# Keg_Cop.net
KiCad netlist of a schematic drawn in EAGLE
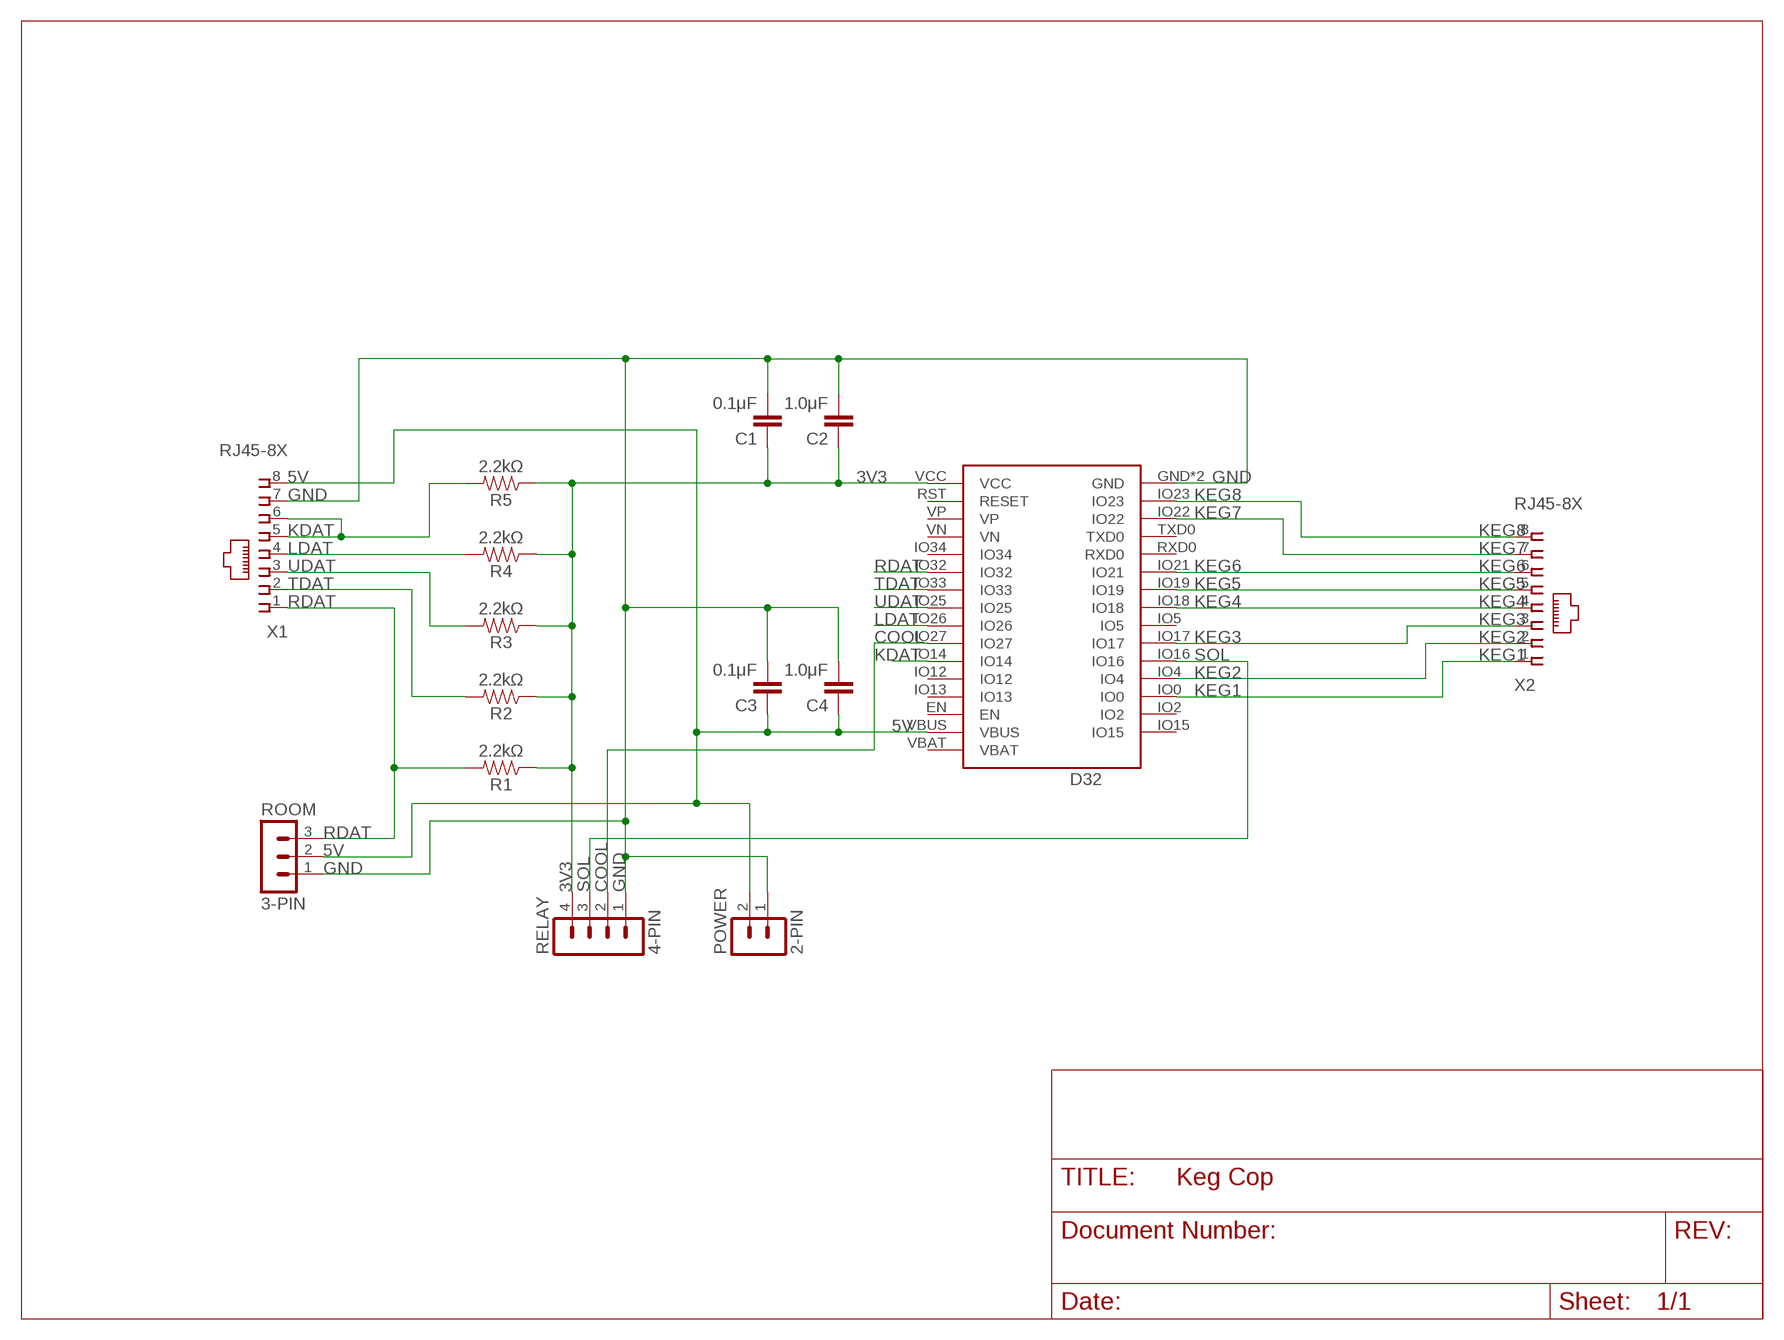
[diagram p0: schematic, sheet 1]

(export (version "E")
  (design (tool "Eeschema 10.0.6"))
  (components
    (comp (ref "C1")
      (value "0.1μF")
      (footprint "eagle-import:CAP_PTH-2.54")
      (libsource (lib "eagle-import") (part "CAP_CERAMIC_2.54"))
    )
    (comp (ref "C2")
      (value "1.0μF")
      (footprint "eagle-import:CAP_PTH-2.54")
      (libsource (lib "eagle-import") (part "CAP_CERAMIC_2.54"))
    )
    (comp (ref "C3")
      (value "0.1μF")
      (footprint "eagle-import:CAP_PTH-2.54")
      (libsource (lib "eagle-import") (part "CAP_CERAMIC_2.54"))
    )
    (comp (ref "C4")
      (value "1.0μF")
      (footprint "eagle-import:CAP_PTH-2.54")
      (libsource (lib "eagle-import") (part "CAP_CERAMIC_2.54"))
    )
    (comp (ref "D32")
      (value "Lolin D32")
      (footprint "eagle-import:D32_NO_BATT")
      (libsource (lib "eagle-import") (part "WEMOS-D32D32_NO_BATT"))
    )
    (comp (ref "POWER")
      (value "2-PIN")
      (footprint "eagle-import:HDR-2_VERT")
      (libsource (lib "eagle-import") (part "HDR-2"))
    )
    (comp (ref "R1")
      (value "2.2kΩ")
      (footprint "eagle-import:AXIAL-0.3")
      (libsource (lib "eagle-import") (part "RESISTORAXIAL-0.3"))
    )
    (comp (ref "R2")
      (value "2.2kΩ")
      (footprint "eagle-import:AXIAL-0.3")
      (libsource (lib "eagle-import") (part "RESISTORAXIAL-0.3"))
    )
    (comp (ref "R3")
      (value "2.2kΩ")
      (footprint "eagle-import:AXIAL-0.3")
      (libsource (lib "eagle-import") (part "RESISTORAXIAL-0.3"))
    )
    (comp (ref "R4")
      (value "2.2kΩ")
      (footprint "eagle-import:AXIAL-0.3")
      (libsource (lib "eagle-import") (part "RESISTORAXIAL-0.3"))
    )
    (comp (ref "R5")
      (value "2.2kΩ")
      (footprint "eagle-import:AXIAL-0.3")
      (libsource (lib "eagle-import") (part "RESISTORAXIAL-0.3"))
    )
    (comp (ref "RELAY")
      (value "4-PIN")
      (footprint "eagle-import:MA04-1")
      (libsource (lib "eagle-import") (part "MA04-1"))
    )
    (comp (ref "ROOM")
      (value "3-PIN")
      (footprint "eagle-import:HDR-3_VERT")
      (libsource (lib "eagle-import") (part "HDR-3"))
    )
    (comp (ref "X1")
      (value "RJ45-8X")
      (footprint "eagle-import:RJ45-NO-SHIELD")
      (libsource (lib "eagle-import") (part "RJ45-8X"))
    )
    (comp (ref "X2")
      (value "RJ45-8X")
      (footprint "eagle-import:RJ45-NO-SHIELD")
      (libsource (lib "eagle-import") (part "RJ45-8X"))
    )
  )
  (nets
    (net (code "1") (name "/3V3") (class "Default")
      (node (ref "C1") (pin "1") (pinfunction "1_1") (pintype "passive"))
      (node (ref "C2") (pin "1") (pinfunction "1_1") (pintype "passive"))
      (node (ref "D32") (pin "VCC") (pinfunction "VCC_VCC") (pintype "power_in"))
      (node (ref "R1") (pin "P$1") (pinfunction "1_P$1") (pintype "passive"))
      (node (ref "R2") (pin "P$1") (pinfunction "1_P$1") (pintype "passive"))
      (node (ref "R3") (pin "P$1") (pinfunction "1_P$1") (pintype "passive"))
      (node (ref "R4") (pin "P$1") (pinfunction "1_P$1") (pintype "passive"))
      (node (ref "R5") (pin "P$1") (pinfunction "1_P$1") (pintype "passive"))
      (node (ref "RELAY") (pin "4") (pinfunction "4_4") (pintype "passive"))
    )
    (net (code "2") (name "/5V") (class "Default")
      (node (ref "C3") (pin "1") (pinfunction "1_1") (pintype "passive"))
      (node (ref "C4") (pin "1") (pinfunction "1_1") (pintype "passive"))
      (node (ref "D32") (pin "VBUS") (pinfunction "VBUS_VBUS") (pintype "bidirectional"))
      (node (ref "POWER") (pin "2") (pinfunction "2_2") (pintype "passive"))
      (node (ref "ROOM") (pin "2") (pinfunction "2_2") (pintype "passive"))
      (node (ref "X1") (pin "8") (pinfunction "8_8") (pintype "passive"))
    )
    (net (code "3") (name "/COOL") (class "Default")
      (node (ref "D32") (pin "IO27") (pinfunction "IO27_IO27") (pintype "bidirectional"))
      (node (ref "RELAY") (pin "2") (pinfunction "2_2") (pintype "passive"))
    )
    (net (code "4") (name "/GND") (class "Default")
      (node (ref "C1") (pin "2") (pinfunction "2_2") (pintype "passive"))
      (node (ref "C2") (pin "2") (pinfunction "2_2") (pintype "passive"))
      (node (ref "C3") (pin "2") (pinfunction "2_2") (pintype "passive"))
      (node (ref "C4") (pin "2") (pinfunction "2_2") (pintype "passive"))
      (node (ref "D32") (pin "GND") (pinfunction "GND_GND") (pintype "power_in"))
      (node (ref "D32") (pin "GND2") (pinfunction "GND_GND2") (pintype "power_in"))
      (node (ref "POWER") (pin "1") (pinfunction "1_1") (pintype "passive"))
      (node (ref "RELAY") (pin "1") (pinfunction "1_1") (pintype "passive"))
      (node (ref "ROOM") (pin "1") (pinfunction "1_1") (pintype "passive"))
      (node (ref "X1") (pin "7") (pinfunction "7_7") (pintype "passive"))
    )
    (net (code "5") (name "/KDAT") (class "Default")
      (node (ref "D32") (pin "IO14") (pinfunction "IO14_IO14") (pintype "bidirectional"))
      (node (ref "R5") (pin "P$2") (pinfunction "2_P$2") (pintype "passive"))
      (node (ref "X1") (pin "5") (pinfunction "5_5") (pintype "passive"))
      (node (ref "X1") (pin "6") (pinfunction "6_6") (pintype "passive"))
    )
    (net (code "6") (name "/KEG1") (class "Default")
      (node (ref "D32") (pin "IO0") (pinfunction "IO0_IO0") (pintype "bidirectional"))
      (node (ref "X2") (pin "1") (pinfunction "1_1") (pintype "passive"))
    )
    (net (code "7") (name "/KEG2") (class "Default")
      (node (ref "D32") (pin "IO4") (pinfunction "IO4_IO4") (pintype "bidirectional"))
      (node (ref "X2") (pin "2") (pinfunction "2_2") (pintype "passive"))
    )
    (net (code "8") (name "/KEG3") (class "Default")
      (node (ref "D32") (pin "IO17") (pinfunction "IO17_IO17") (pintype "bidirectional"))
      (node (ref "X2") (pin "3") (pinfunction "3_3") (pintype "passive"))
    )
    (net (code "9") (name "/KEG4") (class "Default")
      (node (ref "D32") (pin "IO18") (pinfunction "IO18_IO18") (pintype "bidirectional"))
      (node (ref "X2") (pin "4") (pinfunction "4_4") (pintype "passive"))
    )
    (net (code "10") (name "/KEG5") (class "Default")
      (node (ref "D32") (pin "IO19") (pinfunction "IO19_IO19") (pintype "bidirectional"))
      (node (ref "X2") (pin "5") (pinfunction "5_5") (pintype "passive"))
    )
    (net (code "11") (name "/KEG6") (class "Default")
      (node (ref "D32") (pin "IO21") (pinfunction "IO21_IO21") (pintype "bidirectional"))
      (node (ref "X2") (pin "6") (pinfunction "6_6") (pintype "passive"))
    )
    (net (code "12") (name "/KEG7") (class "Default")
      (node (ref "D32") (pin "IO22") (pinfunction "IO22_IO22") (pintype "bidirectional"))
      (node (ref "X2") (pin "7") (pinfunction "7_7") (pintype "passive"))
    )
    (net (code "13") (name "/KEG8") (class "Default")
      (node (ref "D32") (pin "IO23") (pinfunction "IO23_IO23") (pintype "bidirectional"))
      (node (ref "X2") (pin "8") (pinfunction "8_8") (pintype "passive"))
    )
    (net (code "14") (name "/LDAT") (class "Default")
      (node (ref "D32") (pin "IO26") (pinfunction "IO26_IO26") (pintype "bidirectional"))
      (node (ref "R4") (pin "P$2") (pinfunction "2_P$2") (pintype "passive"))
      (node (ref "X1") (pin "4") (pinfunction "4_4") (pintype "passive"))
    )
    (net (code "15") (name "/RDAT") (class "Default")
      (node (ref "D32") (pin "IO32") (pinfunction "IO32_IO32") (pintype "bidirectional"))
      (node (ref "R1") (pin "P$2") (pinfunction "2_P$2") (pintype "passive"))
      (node (ref "ROOM") (pin "3") (pinfunction "3_3") (pintype "passive"))
      (node (ref "X1") (pin "1") (pinfunction "1_1") (pintype "passive"))
    )
    (net (code "16") (name "/SOL") (class "Default")
      (node (ref "D32") (pin "IO16") (pinfunction "IO16_IO16") (pintype "bidirectional"))
      (node (ref "RELAY") (pin "3") (pinfunction "3_3") (pintype "passive"))
    )
    (net (code "17") (name "/TDAT") (class "Default")
      (node (ref "D32") (pin "IO33") (pinfunction "IO33_IO33") (pintype "bidirectional"))
      (node (ref "R2") (pin "P$2") (pinfunction "2_P$2") (pintype "passive"))
      (node (ref "X1") (pin "2") (pinfunction "2_2") (pintype "passive"))
    )
    (net (code "18") (name "/UDAT") (class "Default")
      (node (ref "D32") (pin "IO25") (pinfunction "IO25_IO25") (pintype "bidirectional"))
      (node (ref "R3") (pin "P$2") (pinfunction "2_P$2") (pintype "passive"))
      (node (ref "X1") (pin "3") (pinfunction "3_3") (pintype "passive"))
    )
    (net (code "19") (name "unconnected-(D32-PadEN)") (class "Default")
      (node (ref "D32") (pin "EN") (pinfunction "EN_EN") (pintype "bidirectional"))
    )
    (net (code "20") (name "unconnected-(D32-PadIO2)") (class "Default")
      (node (ref "D32") (pin "IO2") (pinfunction "IO2_IO2") (pintype "bidirectional"))
    )
    (net (code "21") (name "unconnected-(D32-PadIO5)") (class "Default")
      (node (ref "D32") (pin "IO5") (pinfunction "IO5_IO5") (pintype "bidirectional"))
    )
    (net (code "22") (name "unconnected-(D32-PadIO12)") (class "Default")
      (node (ref "D32") (pin "IO12") (pinfunction "IO12_IO12") (pintype "bidirectional"))
    )
    (net (code "23") (name "unconnected-(D32-PadIO13)") (class "Default")
      (node (ref "D32") (pin "IO13") (pinfunction "IO13_IO13") (pintype "bidirectional"))
    )
    (net (code "24") (name "unconnected-(D32-PadIO15)") (class "Default")
      (node (ref "D32") (pin "IO15") (pinfunction "IO15_IO15") (pintype "bidirectional"))
    )
    (net (code "25") (name "unconnected-(D32-PadIO34)") (class "Default")
      (node (ref "D32") (pin "IO34") (pinfunction "IO34_IO34") (pintype "bidirectional"))
    )
    (net (code "26") (name "unconnected-(D32-PadRXD0)") (class "Default")
      (node (ref "D32") (pin "RXD0") (pinfunction "RXD0_RXD0") (pintype "input"))
    )
    (net (code "27") (name "unconnected-(D32-PadTXD0)") (class "Default")
      (node (ref "D32") (pin "TXD0") (pinfunction "TXD0_TXD0") (pintype "output"))
    )
    (net (code "28") (name "unconnected-(D32-PadVBAT)") (class "Default")
      (node (ref "D32") (pin "VBAT") (pinfunction "VBAT_VBAT") (pintype "bidirectional"))
    )
    (net (code "29") (name "unconnected-(D32-PadVN)") (class "Default")
      (node (ref "D32") (pin "VN") (pinfunction "VN_VN") (pintype "bidirectional"))
    )
    (net (code "30") (name "unconnected-(D32-PadVP)") (class "Default")
      (node (ref "D32") (pin "VP") (pinfunction "VP_VP") (pintype "bidirectional"))
    )
    (net (code "31") (name "unconnected-(D32-RESET-PadRST)") (class "Default")
      (node (ref "D32") (pin "RST") (pinfunction "RESET_RST") (pintype "bidirectional"))
    )
  )
)
